# main_v2_0.net
KiCad netlist of a schematic drawn in EAGLE
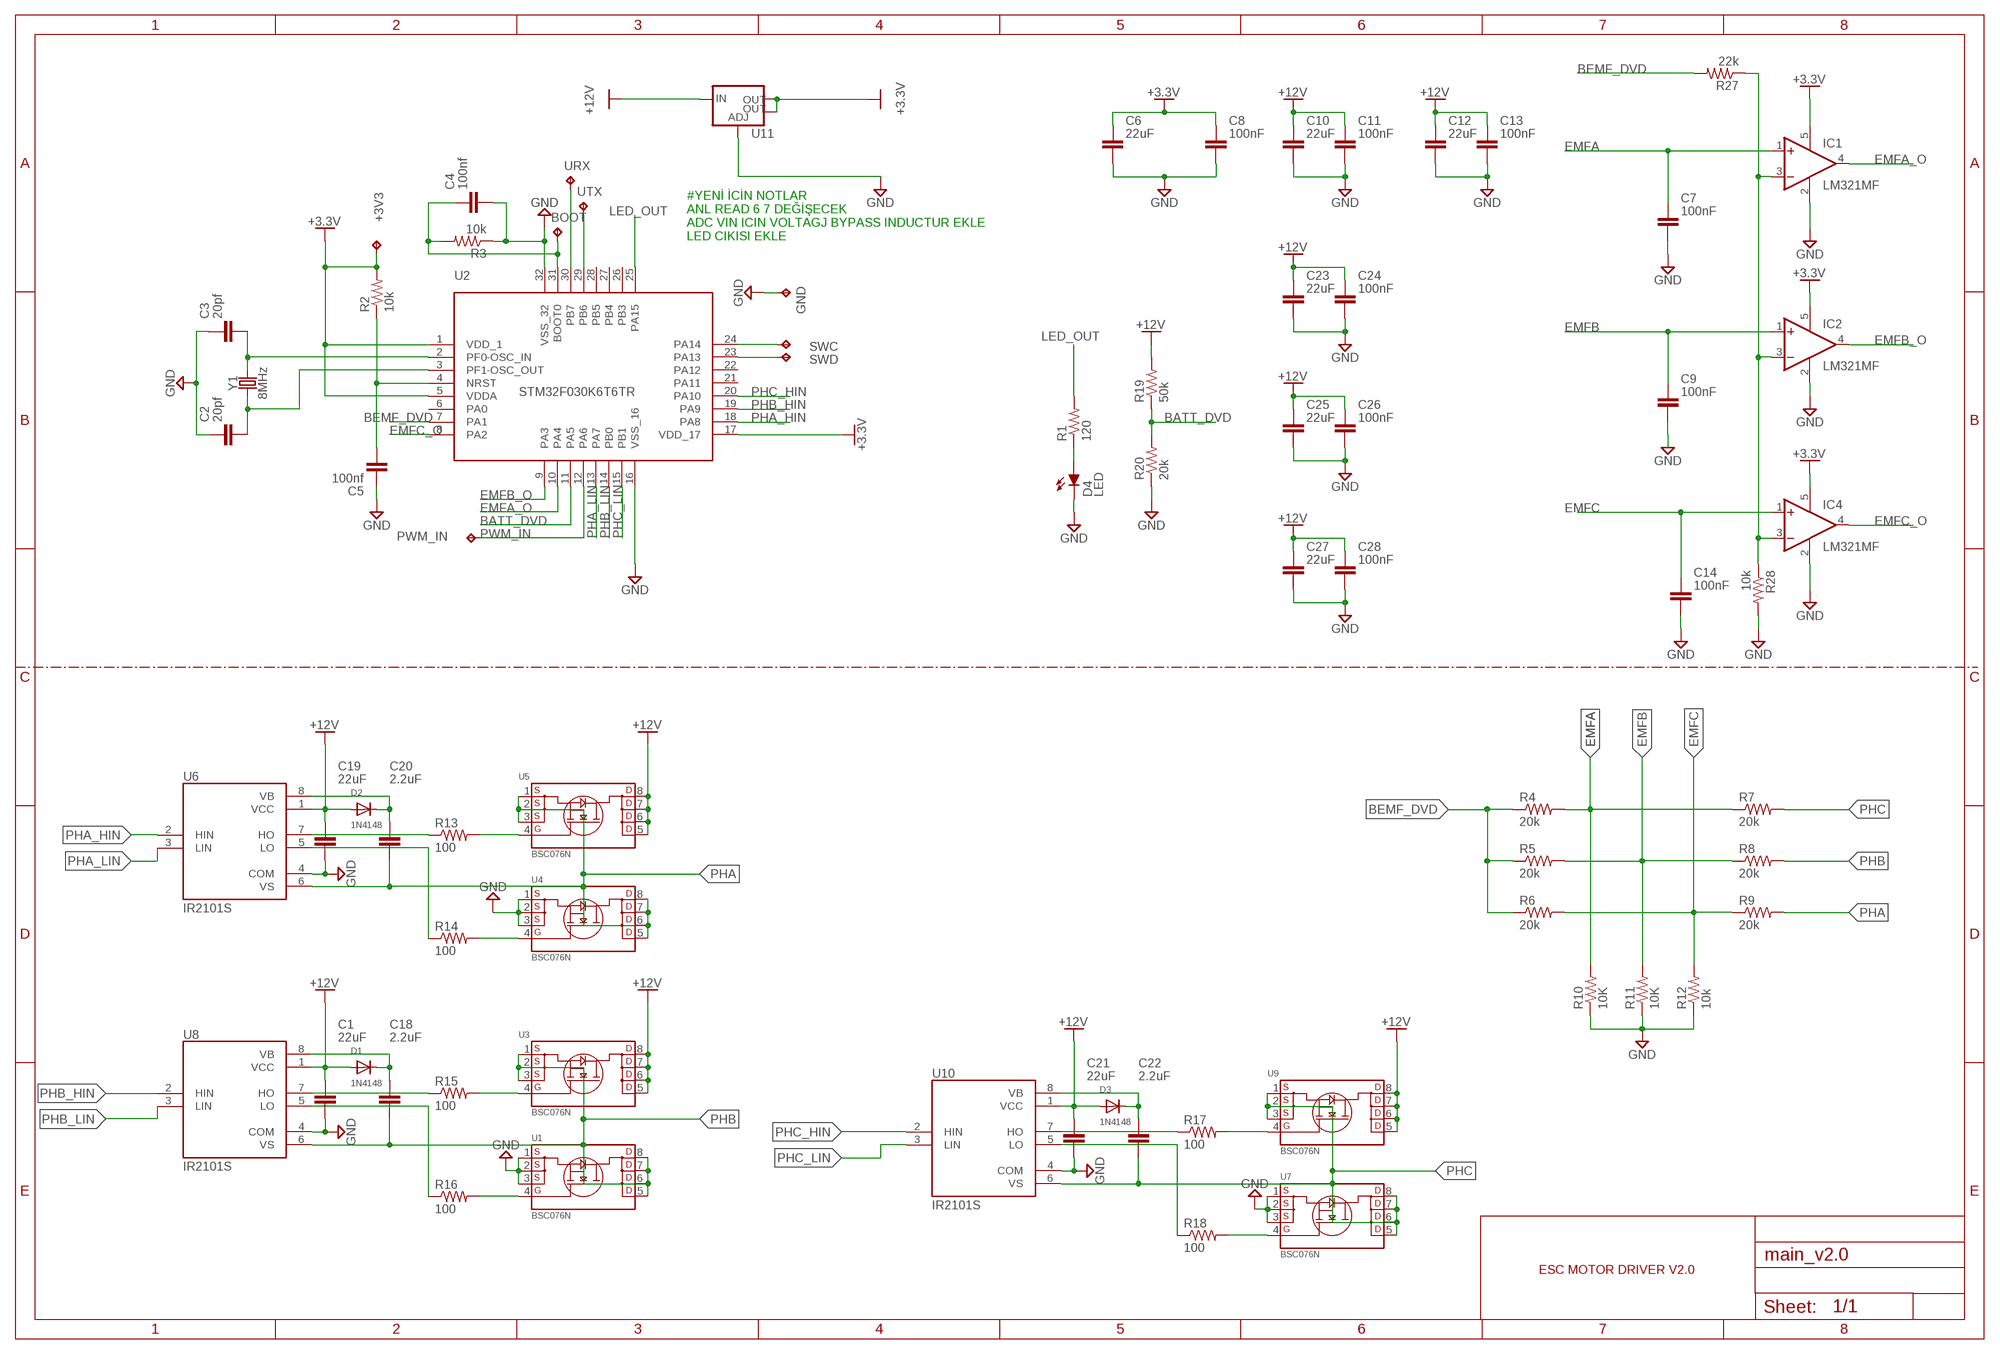
[diagram p0: schematic, sheet 1]

(export (version "E")
  (design (tool "Eeschema 10.0.6"))
  (components
    (comp (ref "+3V3")
      (value "TPTP13R")
      (footprint "eagle-import:TP13R")
      (libsource (lib "eagle-import") (part "TPTP13R"))
    )
    (comp (ref "BOOT")
      (value "TPTP13R")
      (footprint "eagle-import:TP13R")
      (libsource (lib "eagle-import") (part "TPTP13R"))
    )
    (comp (ref "C1")
      (value "22uF")
      (footprint "eagle-import:CAPC3216X135")
      (libsource (lib "eagle-import") (part "CCHIP-1206(3216-METRIC)_"))
    )
    (comp (ref "C2")
      (value "20pf")
      (footprint "eagle-import:CAPC1608X85")
      (libsource (lib "eagle-import") (part "CCHIP-0603(1608-METRIC)_"))
    )
    (comp (ref "C3")
      (value "20pf")
      (footprint "eagle-import:CAPC1608X85")
      (libsource (lib "eagle-import") (part "CCHIP-0603(1608-METRIC)_"))
    )
    (comp (ref "C4")
      (value "100nf")
      (footprint "eagle-import:CAPC2012X110")
      (libsource (lib "eagle-import") (part "CCHIP-0805(2012-METRIC)_"))
    )
    (comp (ref "C5")
      (value "100nf")
      (footprint "eagle-import:CAPC2012X110")
      (libsource (lib "eagle-import") (part "CCHIP-0805(2012-METRIC)_"))
    )
    (comp (ref "C6")
      (value "22uF")
      (footprint "eagle-import:CAPC3216X135")
      (libsource (lib "eagle-import") (part "CCHIP-1206(3216-METRIC)_"))
    )
    (comp (ref "C7")
      (value "100nF")
      (footprint "eagle-import:CAPC2012X110")
      (libsource (lib "eagle-import") (part "CCHIP-0805(2012-METRIC)_"))
    )
    (comp (ref "C8")
      (value "100nF")
      (footprint "eagle-import:CAPC2012X110")
      (libsource (lib "eagle-import") (part "CCHIP-0805(2012-METRIC)_"))
    )
    (comp (ref "C9")
      (value "100nF")
      (footprint "eagle-import:CAPC2012X110")
      (libsource (lib "eagle-import") (part "CCHIP-0805(2012-METRIC)_"))
    )
    (comp (ref "C10")
      (value "22uF")
      (footprint "eagle-import:CAPC3216X135")
      (libsource (lib "eagle-import") (part "CCHIP-1206(3216-METRIC)_"))
    )
    (comp (ref "C11")
      (value "100nF")
      (footprint "eagle-import:CAPC2012X110")
      (libsource (lib "eagle-import") (part "CCHIP-0805(2012-METRIC)_"))
    )
    (comp (ref "C12")
      (value "22uF")
      (footprint "eagle-import:CAPC3216X135")
      (libsource (lib "eagle-import") (part "CCHIP-1206(3216-METRIC)_"))
    )
    (comp (ref "C13")
      (value "100nF")
      (footprint "eagle-import:CAPC2012X110")
      (libsource (lib "eagle-import") (part "CCHIP-0805(2012-METRIC)_"))
    )
    (comp (ref "C14")
      (value "100nF")
      (footprint "eagle-import:CAPC2012X110")
      (libsource (lib "eagle-import") (part "CCHIP-0805(2012-METRIC)_"))
    )
    (comp (ref "C18")
      (value "2.2uF")
      (footprint "eagle-import:CAPC3216X135")
      (libsource (lib "eagle-import") (part "CCHIP-1206(3216-METRIC)_"))
    )
    (comp (ref "C19")
      (value "22uF")
      (footprint "eagle-import:CAPC3216X135")
      (libsource (lib "eagle-import") (part "CCHIP-1206(3216-METRIC)_"))
    )
    (comp (ref "C20")
      (value "2.2uF")
      (footprint "eagle-import:CAPC3216X135")
      (libsource (lib "eagle-import") (part "CCHIP-1206(3216-METRIC)_"))
    )
    (comp (ref "C21")
      (value "22uF")
      (footprint "eagle-import:CAPC3216X135")
      (libsource (lib "eagle-import") (part "CCHIP-1206(3216-METRIC)_"))
    )
    (comp (ref "C22")
      (value "2.2uF")
      (footprint "eagle-import:CAPC3216X135")
      (libsource (lib "eagle-import") (part "CCHIP-1206(3216-METRIC)_"))
    )
    (comp (ref "C23")
      (value "22uF")
      (footprint "eagle-import:CAPC3216X135")
      (libsource (lib "eagle-import") (part "CCHIP-1206(3216-METRIC)_"))
    )
    (comp (ref "C24")
      (value "100nF")
      (footprint "eagle-import:CAPC2012X110")
      (libsource (lib "eagle-import") (part "CCHIP-0805(2012-METRIC)_"))
    )
    (comp (ref "C25")
      (value "22uF")
      (footprint "eagle-import:CAPC3216X135")
      (libsource (lib "eagle-import") (part "CCHIP-1206(3216-METRIC)_"))
    )
    (comp (ref "C26")
      (value "100nF")
      (footprint "eagle-import:CAPC2012X110")
      (libsource (lib "eagle-import") (part "CCHIP-0805(2012-METRIC)_"))
    )
    (comp (ref "C27")
      (value "22uF")
      (footprint "eagle-import:CAPC3216X135")
      (libsource (lib "eagle-import") (part "CCHIP-1206(3216-METRIC)_"))
    )
    (comp (ref "C28")
      (value "100nF")
      (footprint "eagle-import:CAPC2012X110")
      (libsource (lib "eagle-import") (part "CCHIP-0805(2012-METRIC)_"))
    )
    (comp (ref "D1")
      (value "1N4148")
      (footprint "eagle-import:SOD-323F")
      (libsource (lib "eagle-import") (part "DIODESOD-323F"))
    )
    (comp (ref "D2")
      (value "1N4148")
      (footprint "eagle-import:SOD-323F")
      (libsource (lib "eagle-import") (part "DIODESOD-323F"))
    )
    (comp (ref "D3")
      (value "1N4148")
      (footprint "eagle-import:SOD-323F")
      (libsource (lib "eagle-import") (part "DIODESOD-323F"))
    )
    (comp (ref "D4")
      (value "LED")
      (footprint "eagle-import:LED_CHIP-LED0603MP")
      (libsource (lib "eagle-import") (part "LED_LEDCHIP-LED0603MP"))
    )
    (comp (ref "GND")
      (value "TPTP13R")
      (footprint "eagle-import:TP13R")
      (libsource (lib "eagle-import") (part "TPTP13R"))
    )
    (comp (ref "IC1")
      (value "LM321MF")
      (footprint "eagle-import:SOT23-5")
      (libsource (lib "eagle-import") (part "LM321?MF"))
    )
    (comp (ref "IC2")
      (value "LM321MF")
      (footprint "eagle-import:SOT23-5")
      (libsource (lib "eagle-import") (part "LM321?MF"))
    )
    (comp (ref "IC4")
      (value "LM321MF")
      (footprint "eagle-import:SOT23-5")
      (libsource (lib "eagle-import") (part "LM321?MF"))
    )
    (comp (ref "PWM_IN")
      (value "TPTP13R")
      (footprint "eagle-import:TP13R")
      (libsource (lib "eagle-import") (part "TPTP13R"))
    )
    (comp (ref "R1")
      (value "120")
      (footprint "eagle-import:R0603")
      (libsource (lib "eagle-import") (part "R-US_R0603"))
    )
    (comp (ref "R2")
      (value "10k")
      (footprint "eagle-import:R0603")
      (libsource (lib "eagle-import") (part "R-US_R0603"))
    )
    (comp (ref "R3")
      (value "10k")
      (footprint "eagle-import:R0603")
      (libsource (lib "eagle-import") (part "R-US_R0603"))
    )
    (comp (ref "R4")
      (value "20k")
      (footprint "eagle-import:R0603")
      (libsource (lib "eagle-import") (part "R-US_R0603"))
    )
    (comp (ref "R5")
      (value "20k")
      (footprint "eagle-import:R0603")
      (libsource (lib "eagle-import") (part "R-US_R0603"))
    )
    (comp (ref "R6")
      (value "20k")
      (footprint "eagle-import:R0603")
      (libsource (lib "eagle-import") (part "R-US_R0603"))
    )
    (comp (ref "R7")
      (value "20k")
      (footprint "eagle-import:R0603")
      (libsource (lib "eagle-import") (part "R-US_R0603"))
    )
    (comp (ref "R8")
      (value "20k")
      (footprint "eagle-import:R0603")
      (libsource (lib "eagle-import") (part "R-US_R0603"))
    )
    (comp (ref "R9")
      (value "20k")
      (footprint "eagle-import:R0603")
      (libsource (lib "eagle-import") (part "R-US_R0603"))
    )
    (comp (ref "R10")
      (value "10K")
      (footprint "eagle-import:R0603")
      (libsource (lib "eagle-import") (part "R-US_R0603"))
    )
    (comp (ref "R11")
      (value "10K")
      (footprint "eagle-import:R0603")
      (libsource (lib "eagle-import") (part "R-US_R0603"))
    )
    (comp (ref "R12")
      (value "10k")
      (footprint "eagle-import:R0603")
      (libsource (lib "eagle-import") (part "R-US_R0603"))
    )
    (comp (ref "R13")
      (value "100")
      (footprint "eagle-import:R0603")
      (libsource (lib "eagle-import") (part "R-US_R0603"))
    )
    (comp (ref "R14")
      (value "100")
      (footprint "eagle-import:R0603")
      (libsource (lib "eagle-import") (part "R-US_R0603"))
    )
    (comp (ref "R15")
      (value "100")
      (footprint "eagle-import:R0603")
      (libsource (lib "eagle-import") (part "R-US_R0603"))
    )
    (comp (ref "R16")
      (value "100")
      (footprint "eagle-import:R0603")
      (libsource (lib "eagle-import") (part "R-US_R0603"))
    )
    (comp (ref "R17")
      (value "100")
      (footprint "eagle-import:R0603")
      (libsource (lib "eagle-import") (part "R-US_R0603"))
    )
    (comp (ref "R18")
      (value "100")
      (footprint "eagle-import:R0603")
      (libsource (lib "eagle-import") (part "R-US_R0603"))
    )
    (comp (ref "R19")
      (value "50k")
      (footprint "eagle-import:R0603")
      (libsource (lib "eagle-import") (part "R-US_R0603"))
    )
    (comp (ref "R20")
      (value "20k")
      (footprint "eagle-import:R0603")
      (libsource (lib "eagle-import") (part "R-US_R0603"))
    )
    (comp (ref "R27")
      (value "22k")
      (footprint "eagle-import:R0603")
      (libsource (lib "eagle-import") (part "R-US_R0603"))
    )
    (comp (ref "R28")
      (value "10k")
      (footprint "eagle-import:R0603")
      (libsource (lib "eagle-import") (part "R-US_R0603"))
    )
    (comp (ref "SWC")
      (value "TPTP13R")
      (footprint "eagle-import:TP13R")
      (libsource (lib "eagle-import") (part "TPTP13R"))
    )
    (comp (ref "SWD")
      (value "TPTP13R")
      (footprint "eagle-import:TP13R")
      (libsource (lib "eagle-import") (part "TPTP13R"))
    )
    (comp (ref "U1")
      (value "BSC076N")
      (footprint "eagle-import:TRANS_BSC076N06NS3-G")
      (libsource (lib "eagle-import") (part "BSC076N"))
    )
    (comp (ref "U2")
      (value "STM32F030K6T6TR")
      (footprint "eagle-import:32-LQFP")
      (fields
        (field (name "DIGIKEY_PART_NUMBER") "497-17334-6-ND")
        (field (name "MANUFACTURER") "STMicroelectronics")
        (field (name "CREATED_BY") "PCBLayout.com")
      )
      (libsource (lib "eagle-import") (part "STM32F030K6T6TR"))
    )
    (comp (ref "U3")
      (value "BSC076N")
      (footprint "eagle-import:TRANS_BSC076N06NS3-G")
      (libsource (lib "eagle-import") (part "BSC076N"))
    )
    (comp (ref "U4")
      (value "BSC076N")
      (footprint "eagle-import:TRANS_BSC076N06NS3-G")
      (libsource (lib "eagle-import") (part "BSC076N"))
    )
    (comp (ref "U5")
      (value "BSC076N")
      (footprint "eagle-import:TRANS_BSC076N06NS3-G")
      (libsource (lib "eagle-import") (part "BSC076N"))
    )
    (comp (ref "U6")
      (value "IR2101S")
      (footprint "eagle-import:SOIC127P600X175-8N")
      (fields (field (name "MF") "Infineon Technologies"))
      (libsource (lib "eagle-import") (part "IR2101S"))
    )
    (comp (ref "U7")
      (value "BSC076N")
      (footprint "eagle-import:TRANS_BSC076N06NS3-G")
      (libsource (lib "eagle-import") (part "BSC076N"))
    )
    (comp (ref "U8")
      (value "IR2101S")
      (footprint "eagle-import:SOIC127P600X175-8N")
      (fields (field (name "MF") "Infineon Technologies"))
      (libsource (lib "eagle-import") (part "IR2101S"))
    )
    (comp (ref "U9")
      (value "BSC076N")
      (footprint "eagle-import:TRANS_BSC076N06NS3-G")
      (libsource (lib "eagle-import") (part "BSC076N"))
    )
    (comp (ref "U10")
      (value "IR2101S")
      (footprint "eagle-import:SOIC127P600X175-8N")
      (fields (field (name "MF") "Infineon Technologies"))
      (libsource (lib "eagle-import") (part "IR2101S"))
    )
    (comp (ref "U11")
      (value "V_REG_LM1117SOT223")
      (footprint "eagle-import:SOT223")
      (libsource (lib "eagle-import") (part "V_REG_LM1117SOT223"))
    )
    (comp (ref "URX")
      (value "TPTP13R")
      (footprint "eagle-import:TP13R")
      (libsource (lib "eagle-import") (part "TPTP13R"))
    )
    (comp (ref "UTX")
      (value "TPTP13R")
      (footprint "eagle-import:TP13R")
      (libsource (lib "eagle-import") (part "TPTP13R"))
    )
    (comp (ref "Y1")
      (value "8MHz")
      (footprint "eagle-import:CRYSTAL-SMD-5X3.2-4PAD")
      (libsource (lib "eagle-import") (part "CRYSTAL-8MHZSMD-5X3.2"))
    )
  )
  (nets
    (net (code "1") (name "+3.3V") (class "Default")
      (node (ref "+3V3") (pin "TP") (pinfunction "TP_TP") (pintype "input"))
      (node (ref "C6") (pin "1") (pinfunction "1_1") (pintype "passive"))
      (node (ref "C8") (pin "1") (pinfunction "1_1") (pintype "passive"))
      (node (ref "IC1") (pin "5") (pinfunction "V+_5") (pintype "power_in"))
      (node (ref "IC2") (pin "5") (pinfunction "V+_5") (pintype "power_in"))
      (node (ref "IC4") (pin "5") (pinfunction "V+_5") (pintype "power_in"))
      (node (ref "R2") (pin "2") (pinfunction "2_2") (pintype "passive"))
      (node (ref "U11") (pin "2") (pinfunction "OUT_2") (pintype "output"))
      (node (ref "U11") (pin "4") (pinfunction "OUT_4") (pintype "output"))
      (node (ref "U2") (pin "1") (pinfunction "VDD_1_1") (pintype "power_in"))
      (node (ref "U2") (pin "17") (pinfunction "VDD_17_17") (pintype "power_in"))
      (node (ref "U2") (pin "5") (pinfunction "VDDA_5") (pintype "power_in"))
    )
    (net (code "2") (name "+12V") (class "Default")
      (node (ref "C1") (pin "1") (pinfunction "1_1") (pintype "passive"))
      (node (ref "C10") (pin "1") (pinfunction "1_1") (pintype "passive"))
      (node (ref "C11") (pin "1") (pinfunction "1_1") (pintype "passive"))
      (node (ref "C12") (pin "1") (pinfunction "1_1") (pintype "passive"))
      (node (ref "C13") (pin "1") (pinfunction "1_1") (pintype "passive"))
      (node (ref "C19") (pin "1") (pinfunction "1_1") (pintype "passive"))
      (node (ref "C21") (pin "1") (pinfunction "1_1") (pintype "passive"))
      (node (ref "C23") (pin "1") (pinfunction "1_1") (pintype "passive"))
      (node (ref "C24") (pin "1") (pinfunction "1_1") (pintype "passive"))
      (node (ref "C25") (pin "1") (pinfunction "1_1") (pintype "passive"))
      (node (ref "C26") (pin "1") (pinfunction "1_1") (pintype "passive"))
      (node (ref "C27") (pin "1") (pinfunction "1_1") (pintype "passive"))
      (node (ref "C28") (pin "1") (pinfunction "1_1") (pintype "passive"))
      (node (ref "D1") (pin "A") (pinfunction "A_A") (pintype "passive"))
      (node (ref "D2") (pin "A") (pinfunction "A_A") (pintype "passive"))
      (node (ref "D3") (pin "A") (pinfunction "A_A") (pintype "passive"))
      (node (ref "R19") (pin "2") (pinfunction "2_2") (pintype "passive"))
      (node (ref "U10") (pin "1") (pinfunction "VCC_1") (pintype "power_in"))
      (node (ref "U11") (pin "3") (pinfunction "IN_3") (pintype "input"))
      (node (ref "U3") (pin "5") (pinfunction "D1_5") (pintype "power_in"))
      (node (ref "U3") (pin "6") (pinfunction "D2_6") (pintype "power_in"))
      (node (ref "U3") (pin "7") (pinfunction "D3_7") (pintype "power_in"))
      (node (ref "U3") (pin "8") (pinfunction "D4_8") (pintype "power_in"))
      (node (ref "U5") (pin "5") (pinfunction "D1_5") (pintype "power_in"))
      (node (ref "U5") (pin "6") (pinfunction "D2_6") (pintype "power_in"))
      (node (ref "U5") (pin "7") (pinfunction "D3_7") (pintype "power_in"))
      (node (ref "U5") (pin "8") (pinfunction "D4_8") (pintype "power_in"))
      (node (ref "U6") (pin "1") (pinfunction "VCC_1") (pintype "power_in"))
      (node (ref "U8") (pin "1") (pinfunction "VCC_1") (pintype "power_in"))
      (node (ref "U9") (pin "5") (pinfunction "D1_5") (pintype "power_in"))
      (node (ref "U9") (pin "6") (pinfunction "D2_6") (pintype "power_in"))
      (node (ref "U9") (pin "7") (pinfunction "D3_7") (pintype "power_in"))
      (node (ref "U9") (pin "8") (pinfunction "D4_8") (pintype "power_in"))
    )
    (net (code "3") (name "/BATT_DVD") (class "Default")
      (node (ref "R19") (pin "1") (pinfunction "1_1") (pintype "passive"))
      (node (ref "R20") (pin "2") (pinfunction "2_2") (pintype "passive"))
      (node (ref "U2") (pin "11") (pinfunction "PA5_11") (pintype "bidirectional"))
    )
    (net (code "4") (name "/EMFA_O") (class "Default")
      (node (ref "IC1") (pin "4") (pinfunction "OUT_4") (pintype "output"))
      (node (ref "U2") (pin "10") (pinfunction "PA4_10") (pintype "bidirectional"))
    )
    (net (code "5") (name "/EMFB_O") (class "Default")
      (node (ref "IC2") (pin "4") (pinfunction "OUT_4") (pintype "output"))
      (node (ref "U2") (pin "9") (pinfunction "PA3_9") (pintype "bidirectional"))
    )
    (net (code "6") (name "/EMFC_O") (class "Default")
      (node (ref "IC4") (pin "4") (pinfunction "OUT_4") (pintype "output"))
      (node (ref "U2") (pin "8") (pinfunction "PA2_8") (pintype "bidirectional"))
    )
    (net (code "7") (name "/LED_OUT") (class "Default")
      (node (ref "R1") (pin "2") (pinfunction "2_2") (pintype "passive"))
      (node (ref "U2") (pin "25") (pinfunction "PA15_25") (pintype "bidirectional"))
    )
    (net (code "8") (name "/PWM_IN") (class "Default")
      (node (ref "PWM_IN") (pin "TP") (pinfunction "TP_TP") (pintype "input"))
      (node (ref "U2") (pin "12") (pinfunction "PA6_12") (pintype "bidirectional"))
    )
    (net (code "9") (name "BEMF_DVD") (class "Default")
      (node (ref "R27") (pin "2") (pinfunction "2_2") (pintype "passive"))
      (node (ref "R4") (pin "1") (pinfunction "1_1") (pintype "passive"))
      (node (ref "R5") (pin "1") (pinfunction "1_1") (pintype "passive"))
      (node (ref "R6") (pin "1") (pinfunction "1_1") (pintype "passive"))
      (node (ref "U2") (pin "7") (pinfunction "PA1_7") (pintype "bidirectional"))
    )
    (net (code "10") (name "EMFA") (class "Default")
      (node (ref "C7") (pin "1") (pinfunction "1_1") (pintype "passive"))
      (node (ref "IC1") (pin "1") (pinfunction "+IN_1") (pintype "input"))
      (node (ref "R10") (pin "2") (pinfunction "2_2") (pintype "passive"))
      (node (ref "R4") (pin "2") (pinfunction "2_2") (pintype "passive"))
      (node (ref "R7") (pin "1") (pinfunction "1_1") (pintype "passive"))
    )
    (net (code "11") (name "EMFB") (class "Default")
      (node (ref "C9") (pin "1") (pinfunction "1_1") (pintype "passive"))
      (node (ref "IC2") (pin "1") (pinfunction "+IN_1") (pintype "input"))
      (node (ref "R11") (pin "2") (pinfunction "2_2") (pintype "passive"))
      (node (ref "R5") (pin "2") (pinfunction "2_2") (pintype "passive"))
      (node (ref "R8") (pin "1") (pinfunction "1_1") (pintype "passive"))
    )
    (net (code "12") (name "EMFC") (class "Default")
      (node (ref "C14") (pin "1") (pinfunction "1_1") (pintype "passive"))
      (node (ref "IC4") (pin "1") (pinfunction "+IN_1") (pintype "input"))
      (node (ref "R12") (pin "2") (pinfunction "2_2") (pintype "passive"))
      (node (ref "R6") (pin "2") (pinfunction "2_2") (pintype "passive"))
      (node (ref "R9") (pin "1") (pinfunction "1_1") (pintype "passive"))
    )
    (net (code "13") (name "GND") (class "Default")
      (node (ref "C1") (pin "2") (pinfunction "2_2") (pintype "passive"))
      (node (ref "C10") (pin "2") (pinfunction "2_2") (pintype "passive"))
      (node (ref "C11") (pin "2") (pinfunction "2_2") (pintype "passive"))
      (node (ref "C12") (pin "2") (pinfunction "2_2") (pintype "passive"))
      (node (ref "C13") (pin "2") (pinfunction "2_2") (pintype "passive"))
      (node (ref "C14") (pin "2") (pinfunction "2_2") (pintype "passive"))
      (node (ref "C19") (pin "2") (pinfunction "2_2") (pintype "passive"))
      (node (ref "C2") (pin "1") (pinfunction "1_1") (pintype "passive"))
      (node (ref "C21") (pin "2") (pinfunction "2_2") (pintype "passive"))
      (node (ref "C23") (pin "2") (pinfunction "2_2") (pintype "passive"))
      (node (ref "C24") (pin "2") (pinfunction "2_2") (pintype "passive"))
      (node (ref "C25") (pin "2") (pinfunction "2_2") (pintype "passive"))
      (node (ref "C26") (pin "2") (pinfunction "2_2") (pintype "passive"))
      (node (ref "C27") (pin "2") (pinfunction "2_2") (pintype "passive"))
      (node (ref "C28") (pin "2") (pinfunction "2_2") (pintype "passive"))
      (node (ref "C3") (pin "1") (pinfunction "1_1") (pintype "passive"))
      (node (ref "C4") (pin "2") (pinfunction "2_2") (pintype "passive"))
      (node (ref "C5") (pin "1") (pinfunction "1_1") (pintype "passive"))
      (node (ref "C6") (pin "2") (pinfunction "2_2") (pintype "passive"))
      (node (ref "C7") (pin "2") (pinfunction "2_2") (pintype "passive"))
      (node (ref "C8") (pin "2") (pinfunction "2_2") (pintype "passive"))
      (node (ref "C9") (pin "2") (pinfunction "2_2") (pintype "passive"))
      (node (ref "D4") (pin "C") (pinfunction "C_C") (pintype "passive"))
      (node (ref "GND") (pin "TP") (pinfunction "TP_TP") (pintype "input"))
      (node (ref "IC1") (pin "2") (pinfunction "V-_2") (pintype "power_in"))
      (node (ref "IC2") (pin "2") (pinfunction "V-_2") (pintype "power_in"))
      (node (ref "IC4") (pin "2") (pinfunction "V-_2") (pintype "power_in"))
      (node (ref "R10") (pin "1") (pinfunction "1_1") (pintype "passive"))
      (node (ref "R11") (pin "1") (pinfunction "1_1") (pintype "passive"))
      (node (ref "R12") (pin "1") (pinfunction "1_1") (pintype "passive"))
      (node (ref "R20") (pin "1") (pinfunction "1_1") (pintype "passive"))
      (node (ref "R28") (pin "2") (pinfunction "2_2") (pintype "passive"))
      (node (ref "R3") (pin "1") (pinfunction "1_1") (pintype "passive"))
      (node (ref "U1") (pin "1") (pinfunction "S1_1") (pintype "power_in"))
      (node (ref "U1") (pin "2") (pinfunction "S2_2") (pintype "power_in"))
      (node (ref "U1") (pin "3") (pinfunction "S3_3") (pintype "power_in"))
      (node (ref "U10") (pin "4") (pinfunction "COM_4") (pintype "power_in"))
      (node (ref "U11") (pin "1") (pinfunction "ADJ_1") (pintype "input"))
      (node (ref "U2") (pin "16") (pinfunction "VSS_16_16") (pintype "power_in"))
      (node (ref "U2") (pin "32") (pinfunction "VSS_32_32") (pintype "power_in"))
      (node (ref "U4") (pin "1") (pinfunction "S1_1") (pintype "power_in"))
      (node (ref "U4") (pin "2") (pinfunction "S2_2") (pintype "power_in"))
      (node (ref "U4") (pin "3") (pinfunction "S3_3") (pintype "power_in"))
      (node (ref "U6") (pin "4") (pinfunction "COM_4") (pintype "power_in"))
      (node (ref "U7") (pin "1") (pinfunction "S1_1") (pintype "power_in"))
      (node (ref "U7") (pin "2") (pinfunction "S2_2") (pintype "power_in"))
      (node (ref "U7") (pin "3") (pinfunction "S3_3") (pintype "power_in"))
      (node (ref "U8") (pin "4") (pinfunction "COM_4") (pintype "power_in"))
    )
    (net (code "14") (name "Net-(D4-PadA)") (class "Default")
      (node (ref "D4") (pin "A") (pinfunction "A_A") (pintype "passive"))
      (node (ref "R1") (pin "1") (pinfunction "1_1") (pintype "passive"))
    )
    (net (code "15") (name "Net-(IC1--IN)") (class "Default")
      (node (ref "IC1") (pin "3") (pinfunction "-IN_3") (pintype "input"))
      (node (ref "IC2") (pin "3") (pinfunction "-IN_3") (pintype "input"))
      (node (ref "IC4") (pin "3") (pinfunction "-IN_3") (pintype "input"))
      (node (ref "R27") (pin "1") (pinfunction "1_1") (pintype "passive"))
      (node (ref "R28") (pin "1") (pinfunction "1_1") (pintype "passive"))
    )
    (net (code "16") (name "Net-(U1-G)") (class "Default")
      (node (ref "R16") (pin "2") (pinfunction "2_2") (pintype "passive"))
      (node (ref "U1") (pin "4") (pinfunction "G_4") (pintype "passive"))
    )
    (net (code "17") (name "Net-(U2-BOOT0)") (class "Default")
      (node (ref "BOOT") (pin "TP") (pinfunction "TP_TP") (pintype "input"))
      (node (ref "C4") (pin "1") (pinfunction "1_1") (pintype "passive"))
      (node (ref "R3") (pin "2") (pinfunction "2_2") (pintype "passive"))
      (node (ref "U2") (pin "31") (pinfunction "BOOT0_31") (pintype "input"))
    )
    (net (code "18") (name "Net-(U2-NRST)") (class "Default")
      (node (ref "C5") (pin "2") (pinfunction "2_2") (pintype "passive"))
      (node (ref "R2") (pin "1") (pinfunction "1_1") (pintype "passive"))
      (node (ref "U2") (pin "4") (pinfunction "NRST_4") (pintype "bidirectional"))
    )
    (net (code "19") (name "Net-(U2-PA13)") (class "Default")
      (node (ref "SWD") (pin "TP") (pinfunction "TP_TP") (pintype "input"))
      (node (ref "U2") (pin "23") (pinfunction "PA13_23") (pintype "bidirectional"))
    )
    (net (code "20") (name "Net-(U2-PA14)") (class "Default")
      (node (ref "SWC") (pin "TP") (pinfunction "TP_TP") (pintype "input"))
      (node (ref "U2") (pin "24") (pinfunction "PA14_24") (pintype "bidirectional"))
    )
    (net (code "21") (name "Net-(U2-PB6)") (class "Default")
      (node (ref "U2") (pin "29") (pinfunction "PB6_29") (pintype "bidirectional"))
      (node (ref "UTX") (pin "TP") (pinfunction "TP_TP") (pintype "input"))
    )
    (net (code "22") (name "Net-(U2-PB7)") (class "Default")
      (node (ref "U2") (pin "30") (pinfunction "PB7_30") (pintype "bidirectional"))
      (node (ref "URX") (pin "TP") (pinfunction "TP_TP") (pintype "input"))
    )
    (net (code "23") (name "Net-(U2-PF0-OSC_IN)") (class "Default")
      (node (ref "C3") (pin "2") (pinfunction "2_2") (pintype "passive"))
      (node (ref "U2") (pin "2") (pinfunction "PF0-OSC_IN_2") (pintype "bidirectional"))
      (node (ref "Y1") (pin "3") (pinfunction "2_3") (pintype "passive"))
    )
    (net (code "24") (name "Net-(U2-PF1-OSC_OUT)") (class "Default")
      (node (ref "C2") (pin "2") (pinfunction "2_2") (pintype "passive"))
      (node (ref "U2") (pin "3") (pinfunction "PF1-OSC_OUT_3") (pintype "bidirectional"))
      (node (ref "Y1") (pin "1") (pinfunction "1_1") (pintype "passive"))
    )
    (net (code "25") (name "Net-(U3-G)") (class "Default")
      (node (ref "R15") (pin "2") (pinfunction "2_2") (pintype "passive"))
      (node (ref "U3") (pin "4") (pinfunction "G_4") (pintype "passive"))
    )
    (net (code "26") (name "Net-(U4-G)") (class "Default")
      (node (ref "R14") (pin "2") (pinfunction "2_2") (pintype "passive"))
      (node (ref "U4") (pin "4") (pinfunction "G_4") (pintype "passive"))
    )
    (net (code "27") (name "Net-(U5-G)") (class "Default")
      (node (ref "R13") (pin "2") (pinfunction "2_2") (pintype "passive"))
      (node (ref "U5") (pin "4") (pinfunction "G_4") (pintype "passive"))
    )
    (net (code "28") (name "Net-(U6-HO)") (class "Default")
      (node (ref "R13") (pin "1") (pinfunction "1_1") (pintype "passive"))
      (node (ref "U6") (pin "7") (pinfunction "HO_7") (pintype "output"))
    )
    (net (code "29") (name "Net-(U6-LO)") (class "Default")
      (node (ref "R14") (pin "1") (pinfunction "1_1") (pintype "passive"))
      (node (ref "U6") (pin "5") (pinfunction "LO_5") (pintype "output"))
    )
    (net (code "30") (name "Net-(U6-VB)") (class "Default")
      (node (ref "C20") (pin "1") (pinfunction "1_1") (pintype "passive"))
      (node (ref "D2") (pin "C") (pinfunction "C_C") (pintype "passive"))
      (node (ref "U6") (pin "8") (pinfunction "VB_8") (pintype "power_in"))
    )
    (net (code "31") (name "Net-(U7-G)") (class "Default")
      (node (ref "R18") (pin "2") (pinfunction "2_2") (pintype "passive"))
      (node (ref "U7") (pin "4") (pinfunction "G_4") (pintype "passive"))
    )
    (net (code "32") (name "Net-(U8-HO)") (class "Default")
      (node (ref "R15") (pin "1") (pinfunction "1_1") (pintype "passive"))
      (node (ref "U8") (pin "7") (pinfunction "HO_7") (pintype "output"))
    )
    (net (code "33") (name "Net-(U8-LO)") (class "Default")
      (node (ref "R16") (pin "1") (pinfunction "1_1") (pintype "passive"))
      (node (ref "U8") (pin "5") (pinfunction "LO_5") (pintype "output"))
    )
    (net (code "34") (name "Net-(U8-VB)") (class "Default")
      (node (ref "C18") (pin "1") (pinfunction "1_1") (pintype "passive"))
      (node (ref "D1") (pin "C") (pinfunction "C_C") (pintype "passive"))
      (node (ref "U8") (pin "8") (pinfunction "VB_8") (pintype "power_in"))
    )
    (net (code "35") (name "Net-(U9-G)") (class "Default")
      (node (ref "R17") (pin "2") (pinfunction "2_2") (pintype "passive"))
      (node (ref "U9") (pin "4") (pinfunction "G_4") (pintype "passive"))
    )
    (net (code "36") (name "Net-(U10-HO)") (class "Default")
      (node (ref "R17") (pin "1") (pinfunction "1_1") (pintype "passive"))
      (node (ref "U10") (pin "7") (pinfunction "HO_7") (pintype "output"))
    )
    (net (code "37") (name "Net-(U10-LO)") (class "Default")
      (node (ref "R18") (pin "1") (pinfunction "1_1") (pintype "passive"))
      (node (ref "U10") (pin "5") (pinfunction "LO_5") (pintype "output"))
    )
    (net (code "38") (name "Net-(U10-VB)") (class "Default")
      (node (ref "C22") (pin "1") (pinfunction "1_1") (pintype "passive"))
      (node (ref "D3") (pin "C") (pinfunction "C_C") (pintype "passive"))
      (node (ref "U10") (pin "8") (pinfunction "VB_8") (pintype "power_in"))
    )
    (net (code "39") (name "PHA") (class "Default")
      (node (ref "C20") (pin "2") (pinfunction "2_2") (pintype "passive"))
      (node (ref "R9") (pin "2") (pinfunction "2_2") (pintype "passive"))
      (node (ref "U4") (pin "5") (pinfunction "D1_5") (pintype "power_in"))
      (node (ref "U4") (pin "6") (pinfunction "D2_6") (pintype "power_in"))
      (node (ref "U4") (pin "7") (pinfunction "D3_7") (pintype "power_in"))
      (node (ref "U4") (pin "8") (pinfunction "D4_8") (pintype "power_in"))
      (node (ref "U5") (pin "1") (pinfunction "S1_1") (pintype "power_in"))
      (node (ref "U5") (pin "2") (pinfunction "S2_2") (pintype "power_in"))
      (node (ref "U5") (pin "3") (pinfunction "S3_3") (pintype "power_in"))
      (node (ref "U6") (pin "6") (pinfunction "VS_6") (pintype "power_in"))
    )
    (net (code "40") (name "PHA_HIN") (class "Default")
      (node (ref "U2") (pin "18") (pinfunction "PA8_18") (pintype "bidirectional"))
      (node (ref "U6") (pin "2") (pinfunction "HIN_2") (pintype "input"))
    )
    (net (code "41") (name "PHA_LIN") (class "Default")
      (node (ref "U2") (pin "13") (pinfunction "PA7_13") (pintype "bidirectional"))
      (node (ref "U6") (pin "3") (pinfunction "LIN_3") (pintype "input"))
    )
    (net (code "42") (name "PHB") (class "Default")
      (node (ref "C18") (pin "2") (pinfunction "2_2") (pintype "passive"))
      (node (ref "R8") (pin "2") (pinfunction "2_2") (pintype "passive"))
      (node (ref "U1") (pin "5") (pinfunction "D1_5") (pintype "power_in"))
      (node (ref "U1") (pin "6") (pinfunction "D2_6") (pintype "power_in"))
      (node (ref "U1") (pin "7") (pinfunction "D3_7") (pintype "power_in"))
      (node (ref "U1") (pin "8") (pinfunction "D4_8") (pintype "power_in"))
      (node (ref "U3") (pin "1") (pinfunction "S1_1") (pintype "power_in"))
      (node (ref "U3") (pin "2") (pinfunction "S2_2") (pintype "power_in"))
      (node (ref "U3") (pin "3") (pinfunction "S3_3") (pintype "power_in"))
      (node (ref "U8") (pin "6") (pinfunction "VS_6") (pintype "power_in"))
    )
    (net (code "43") (name "PHB_HIN") (class "Default")
      (node (ref "U2") (pin "19") (pinfunction "PA9_19") (pintype "bidirectional"))
      (node (ref "U8") (pin "2") (pinfunction "HIN_2") (pintype "input"))
    )
    (net (code "44") (name "PHB_LIN") (class "Default")
      (node (ref "U2") (pin "14") (pinfunction "PB0_14") (pintype "bidirectional"))
      (node (ref "U8") (pin "3") (pinfunction "LIN_3") (pintype "input"))
    )
    (net (code "45") (name "PHC") (class "Default")
      (node (ref "C22") (pin "2") (pinfunction "2_2") (pintype "passive"))
      (node (ref "R7") (pin "2") (pinfunction "2_2") (pintype "passive"))
      (node (ref "U10") (pin "6") (pinfunction "VS_6") (pintype "power_in"))
      (node (ref "U7") (pin "5") (pinfunction "D1_5") (pintype "power_in"))
      (node (ref "U7") (pin "6") (pinfunction "D2_6") (pintype "power_in"))
      (node (ref "U7") (pin "7") (pinfunction "D3_7") (pintype "power_in"))
      (node (ref "U7") (pin "8") (pinfunction "D4_8") (pintype "power_in"))
      (node (ref "U9") (pin "1") (pinfunction "S1_1") (pintype "power_in"))
      (node (ref "U9") (pin "2") (pinfunction "S2_2") (pintype "power_in"))
      (node (ref "U9") (pin "3") (pinfunction "S3_3") (pintype "power_in"))
    )
    (net (code "46") (name "PHC_HIN") (class "Default")
      (node (ref "U10") (pin "2") (pinfunction "HIN_2") (pintype "input"))
      (node (ref "U2") (pin "20") (pinfunction "PA10_20") (pintype "bidirectional"))
    )
    (net (code "47") (name "PHC_LIN") (class "Default")
      (node (ref "U10") (pin "3") (pinfunction "LIN_3") (pintype "input"))
      (node (ref "U2") (pin "15") (pinfunction "PB1_15") (pintype "bidirectional"))
    )
    (net (code "48") (name "unconnected-(U2-PA0-Pad6)") (class "Default")
      (node (ref "U2") (pin "6") (pinfunction "PA0_6") (pintype "bidirectional"))
    )
    (net (code "49") (name "unconnected-(U2-PA11-Pad21)") (class "Default")
      (node (ref "U2") (pin "21") (pinfunction "PA11_21") (pintype "bidirectional"))
    )
    (net (code "50") (name "unconnected-(U2-PA12-Pad22)") (class "Default")
      (node (ref "U2") (pin "22") (pinfunction "PA12_22") (pintype "bidirectional"))
    )
    (net (code "51") (name "unconnected-(U2-PB3-Pad26)") (class "Default")
      (node (ref "U2") (pin "26") (pinfunction "PB3_26") (pintype "bidirectional"))
    )
    (net (code "52") (name "unconnected-(U2-PB4-Pad27)") (class "Default")
      (node (ref "U2") (pin "27") (pinfunction "PB4_27") (pintype "bidirectional"))
    )
    (net (code "53") (name "unconnected-(U2-PB5-Pad28)") (class "Default")
      (node (ref "U2") (pin "28") (pinfunction "PB5_28") (pintype "bidirectional"))
    )
  )
)
